# Clock_Buffer.net
KiCad netlist of a schematic drawn in Altium Designer
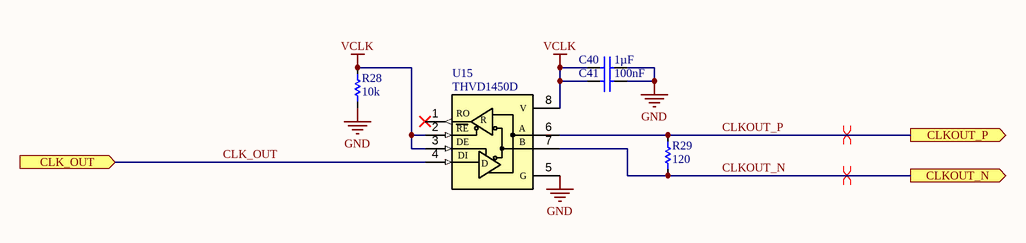
[diagram p0: Clock Buffer.SchDoc]

(export (version "E")
  (design (tool "Eeschema 10.0.6"))
  (components
    (comp (ref "C40")
      (value "1µF")
      (footprint "CAP_CHIP_0603")
      (description "0603 Multilayer Ceramic Capacitors MLCC")
      (fields (field (name "PARTNUMBER") "CL10A105KB8NNNC") (field (name "TOLERANCE") "10%"))
      (libsource (lib "Sainsbury Wellcome Centre") (part "Cap"))
    )
    (comp (ref "C41")
      (value "100nF")
      (footprint "CAP_CHIP_0603")
      (description "0603 Multilayer Ceramic Capacitors MLCC")
      (fields (field (name "TOLERANCE") "10%") (field (name "PARTNUMBER") "CC0603KRX7R9BB104"))
      (libsource (lib "Sainsbury Wellcome Centre") (part "Cap"))
    )
    (comp (ref "R28")
      (value "10k")
      (footprint "RES_CHIP_0603")
      (description "100mW Thick Film Resistors 75V ±100ppm/℃ ±1% 0603 Chip Resistor")
      (fields (field (name "PARTNUMBER") "0603WAF1002T5E") (field (name "TOLERANCE") "1%"))
      (libsource (lib "Sainsbury Wellcome Centre") (part "Res"))
    )
    (comp (ref "R29")
      (value "120")
      (footprint "RES_CHIP_0603")
      (description "100mW Thick Film Resistors 75V ±100ppm/℃ ±1% 0603 Chip Resistor")
      (fields (field (name "PARTNUMBER") "0603WAF1200T5E") (field (name "TOLERANCE") "1%"))
      (libsource (lib "Sainsbury Wellcome Centre") (part "Res"))
    )
    (comp (ref "U15")
      (value "THVD1450D")
      (footprint "VSSOP8_3X3_0.65E")
      (description "3.3-V to 5-V RS-485 transceiver with ±18-kV IEC ESD protection 8-VSSOP -40 to 125")
      (fields (field (name "PARTNUMBER") "THVD1450DGKR"))
      (libsource (lib "Sainsbury Wellcome Centre") (part "THVD1450"))
    )
  )
  (nets
    (net (code "1") (name "/CLKOUT_N") (class "Default")
      (node (ref "R29") (pin "1") (pinfunction "1_1") (pintype "passive"))
      (node (ref "U15") (pin "7") (pinfunction "B_7") (pintype "passive"))
    )
    (net (code "2") (name "/CLKOUT_P") (class "Default")
      (node (ref "R29") (pin "2") (pinfunction "2_2") (pintype "passive"))
      (node (ref "U15") (pin "6") (pinfunction "A_6") (pintype "passive"))
    )
    (net (code "3") (name "/CLK_OUT") (class "Default")
      (node (ref "U15") (pin "4") (pinfunction "D_4") (pintype "input"))
    )
    (net (code "4") (name "GND") (class "Default")
      (node (ref "C40") (pin "1") (pinfunction "1_1") (pintype "passive"))
      (node (ref "C41") (pin "1") (pinfunction "1_1") (pintype "passive"))
      (node (ref "R28") (pin "1") (pinfunction "1_1") (pintype "passive"))
      (node (ref "U15") (pin "5") (pinfunction "G_5") (pintype "power_in"))
    )
    (net (code "5") (name "VCLK") (class "Default")
      (node (ref "C40") (pin "2") (pinfunction "2_2") (pintype "passive"))
      (node (ref "C41") (pin "2") (pinfunction "2_2") (pintype "passive"))
      (node (ref "R28") (pin "2") (pinfunction "2_2") (pintype "passive"))
      (node (ref "U15") (pin "2") (pinfunction "~{RE}_2") (pintype "input"))
      (node (ref "U15") (pin "3") (pinfunction "DE_3") (pintype "input"))
      (node (ref "U15") (pin "8") (pinfunction "V_8") (pintype "power_in"))
    )
    (net (code "6") (name "unconnected-(U15-RO-Pad1)") (class "Default")
      (node (ref "U15") (pin "1") (pinfunction "RO_1") (pintype "output+no_connect"))
    )
  )
)
